# THS7002CPWP_Schematic.net
KiCad netlist of a schematic drawn in Altium Designer
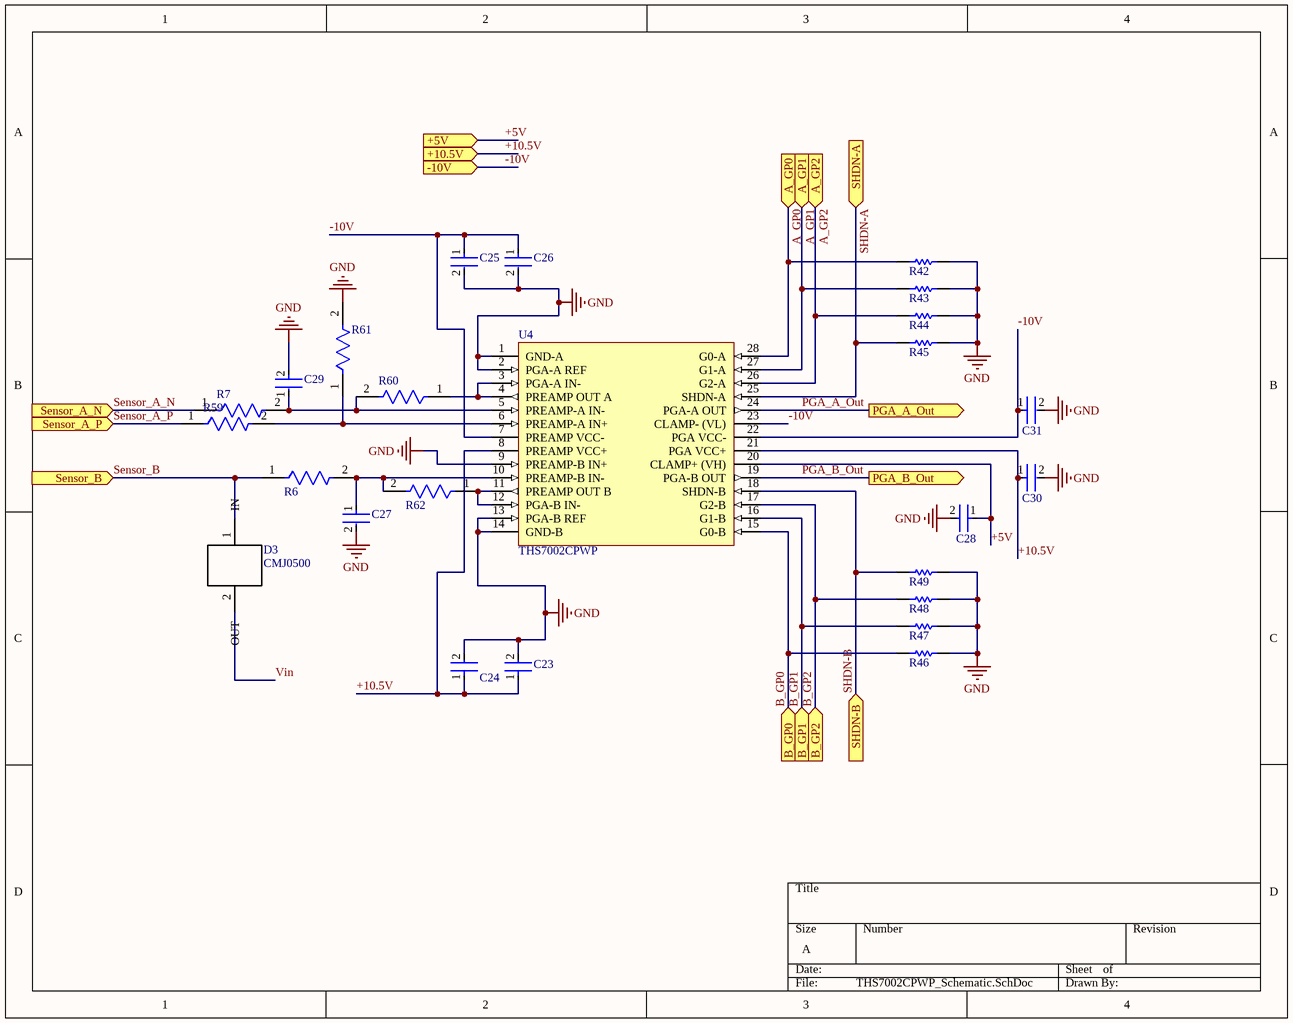
[diagram p0: THS7002CPWP_Schematic.SchDoc]

(export (version "E")
  (design (tool "Eeschema 10.0.6"))
  (components
    (comp (ref "C23")
      (value "~")
      (footprint "FP-C2012-060-0_2-IPC_A")
      (description "Multilayer Ceramic Capacitors 6.8μF ±10% 10V JB SMD 0805")
      (fields (field (name "TOLERANCE") "10%"))
      (libsource (lib "Capacitors") (part "CMP-08246-004641-1"))
    )
    (comp (ref "C24")
      (value "CC0603KRX7R7BB104")
      (footprint "FP-CC0603-DA-MFG")
      (description "CAP CER 0.1UF 16V X7R 0603")
      (fields
        (field (name "OCTOPART") "https://octopart.com/cc0603krx7r7bb104-yageo-192941")
        (field (name "TOLERANCE") "0.1")
      )
      (libsource (lib "Altium Content Vault") (part "11868f565c42a9108669ba33697ecf6"))
    )
    (comp (ref "C25")
      (value "CC0603KRX7R7BB104")
      (footprint "FP-CC0603-DA-MFG")
      (description "CAP CER 0.1UF 16V X7R 0603")
      (fields
        (field (name "OCTOPART") "https://octopart.com/cc0603krx7r7bb104-yageo-192941")
        (field (name "TOLERANCE") "0.1")
      )
      (libsource (lib "Altium Content Vault") (part "11868f565c42a9108669ba33697ecf6"))
    )
    (comp (ref "C26")
      (value "~")
      (footprint "FP-C2012-060-0_2-IPC_A")
      (description "Multilayer Ceramic Capacitors 6.8μF ±10% 10V JB SMD 0805")
      (fields (field (name "TOLERANCE") "10%"))
      (libsource (lib "Capacitors") (part "b4654b650e69147ec39a6b967a45e02"))
    )
    (comp (ref "C27")
      (value "GRM2195C1H622JA01D")
      (footprint "FP-GRM219-0_1-IPC_C")
      (description "Chip Multilayer Ceramic Capacitors for General Purpose, 0805, 6200pF, C0G, 30ppm/°C, 5%, 50V")
      (fields (field (name "TOLERANCE") "5%") (field (name "VOLTAGE") "50V"))
      (libsource (lib "Altium Content Vault") (part "02cd4be3c70576c341d710602a673aa"))
    )
    (comp (ref "C28")
      (value "~")
      (footprint "FP-C2012-060-0_2-IPC_A")
      (description "Multilayer Ceramic Capacitors 6.8μF ±10% 10V JB SMD 0805")
      (fields (field (name "TOLERANCE") "10%"))
      (libsource (lib "Capacitors") (part "b4654b650e69147ec39a6b967a45e02"))
    )
    (comp (ref "C29")
      (value "GRM2165C1H302JA01D")
      (footprint "FP-GRM216-0_1-IPC_A")
      (description "Chip Multilayer Ceramic Capacitors for General Purpose, 0805, 3000pF, C0G, 30ppm/°C, 5%, 50V")
      (fields (field (name "VOLTAGE") "50V") (field (name "TOLERANCE") "5%"))
      (libsource (lib "Altium Content Vault") (part "236180d848d6139a670b325ea6854c9"))
    )
    (comp (ref "C30")
      (value "CC0603KRX7R7BB104")
      (footprint "FP-CC0603-DA-MFG")
      (description "CAP CER 0.1UF 16V X7R 0603")
      (fields
        (field (name "OCTOPART") "https://octopart.com/cc0603krx7r7bb104-yageo-192941")
        (field (name "TOLERANCE") "0.1")
      )
      (libsource (lib "Altium Content Vault") (part "11868f565c42a9108669ba33697ecf6"))
    )
    (comp (ref "C31")
      (value "CC0603KRX7R7BB104")
      (footprint "FP-CC0603-DA-MFG")
      (description "CAP CER 0.1UF 16V X7R 0603")
      (fields
        (field (name "OCTOPART") "https://octopart.com/cc0603krx7r7bb104-yageo-192941")
        (field (name "TOLERANCE") "0.1")
      )
      (libsource (lib "Altium Content Vault") (part "11868f565c42a9108669ba33697ecf6"))
    )
    (comp (ref "D3")
      (value "CMJ0500")
      (footprint "CMJ2000_Footprint")
      (description "CMJ0500: DIODE CUR REG 100V 0.5mA 500MW")
      (libsource (lib "CMJ2000_Schematic") (part "CMJ2000/0130"))
    )
    (comp (ref "R6")
      (value "CRCW0603499RFKEA")
      (footprint "FP-CRCW0603-e3-MFG")
      (description "RES Thick Film, 499Ω, 1%, 0.1W, 100ppm/°C, 0603")
      (fields (field (name "TOLERANCE") "1%"))
      (libsource (lib "Altium Content Vault") (part "1029c3af85768c4190bb7ad29bc67b5"))
    )
    (comp (ref "R7")
      (value "CRCW0603499RFKEA")
      (footprint "FP-CRCW0603-e3-MFG")
      (description "RES Thick Film, 499Ω, 1%, 0.1W, 100ppm/°C, 0603")
      (fields (field (name "TOLERANCE") "1%"))
      (libsource (lib "Altium Content Vault") (part "1029c3af85768c4190bb7ad29bc67b5"))
    )
    (comp (ref "R42")
      (value "RC0603FR-073K3L")
      (footprint "RESC1608X55X25ML10T15")
      (description "Chip Resistor, 3.3 KOhm, +/- 1%, 0.1 W, -55 to 155 degC, 0603 (1608 Metric), RoHS, Tape and Reel")
      (fields (field (name "MANUFACTURER") "Yageo") (field (name "TOLERANCE") "1%"))
      (libsource (lib "Altium Content Vault") (part "RES-2"))
    )
    (comp (ref "R43")
      (value "RC0603FR-073K3L")
      (footprint "RESC1608X55X25ML10T15")
      (description "Chip Resistor, 3.3 KOhm, +/- 1%, 0.1 W, -55 to 155 degC, 0603 (1608 Metric), RoHS, Tape and Reel")
      (fields (field (name "MANUFACTURER") "Yageo") (field (name "TOLERANCE") "1%"))
      (libsource (lib "Altium Content Vault") (part "RES-2"))
    )
    (comp (ref "R44")
      (value "RC0603FR-073K3L")
      (footprint "RESC1608X55X25ML10T15")
      (description "Chip Resistor, 3.3 KOhm, +/- 1%, 0.1 W, -55 to 155 degC, 0603 (1608 Metric), RoHS, Tape and Reel")
      (fields (field (name "MANUFACTURER") "Yageo") (field (name "TOLERANCE") "1%"))
      (libsource (lib "Altium Content Vault") (part "RES-2"))
    )
    (comp (ref "R45")
      (value "RC0603FR-073K3L")
      (footprint "RESC1608X55X25ML10T15")
      (description "Chip Resistor, 3.3 KOhm, +/- 1%, 0.1 W, -55 to 155 degC, 0603 (1608 Metric), RoHS, Tape and Reel")
      (fields (field (name "MANUFACTURER") "Yageo") (field (name "TOLERANCE") "1%"))
      (libsource (lib "Altium Content Vault") (part "RES-2"))
    )
    (comp (ref "R46")
      (value "RC0603FR-073K3L")
      (footprint "RESC1608X55X25ML10T15")
      (description "Chip Resistor, 3.3 KOhm, +/- 1%, 0.1 W, -55 to 155 degC, 0603 (1608 Metric), RoHS, Tape and Reel")
      (fields (field (name "MANUFACTURER") "Yageo") (field (name "TOLERANCE") "1%"))
      (libsource (lib "Altium Content Vault") (part "RES-2"))
    )
    (comp (ref "R47")
      (value "RC0603FR-073K3L")
      (footprint "RESC1608X55X25ML10T15")
      (description "Chip Resistor, 3.3 KOhm, +/- 1%, 0.1 W, -55 to 155 degC, 0603 (1608 Metric), RoHS, Tape and Reel")
      (fields (field (name "MANUFACTURER") "Yageo") (field (name "TOLERANCE") "1%"))
      (libsource (lib "Altium Content Vault") (part "RES-2"))
    )
    (comp (ref "R48")
      (value "RC0603FR-073K3L")
      (footprint "RESC1608X55X25ML10T15")
      (description "Chip Resistor, 3.3 KOhm, +/- 1%, 0.1 W, -55 to 155 degC, 0603 (1608 Metric), RoHS, Tape and Reel")
      (fields (field (name "MANUFACTURER") "Yageo") (field (name "TOLERANCE") "1%"))
      (libsource (lib "Altium Content Vault") (part "RES-2"))
    )
    (comp (ref "R49")
      (value "RC0603FR-073K3L")
      (footprint "RESC1608X55X25ML10T15")
      (description "Chip Resistor, 3.3 KOhm, +/- 1%, 0.1 W, -55 to 155 degC, 0603 (1608 Metric), RoHS, Tape and Reel")
      (fields (field (name "MANUFACTURER") "Yageo") (field (name "TOLERANCE") "1%"))
      (libsource (lib "Altium Content Vault") (part "RES-2"))
    )
    (comp (ref "R59")
      (value "CRCW0603499RFKEA")
      (footprint "FP-CRCW0603-e3-MFG")
      (description "RES Thick Film, 499Ω, 1%, 0.1W, 100ppm/°C, 0603")
      (fields (field (name "TOLERANCE") "1%"))
      (libsource (lib "Altium Content Vault") (part "1029c3af85768c4190bb7ad29bc67b5"))
    )
    (comp (ref "R60")
      (value "CRCW0603499RFKEA")
      (footprint "FP-CRCW0603-e3-MFG")
      (description "RES Thick Film, 499Ω, 1%, 0.1W, 100ppm/°C, 0603")
      (fields (field (name "TOLERANCE") "1%"))
      (libsource (lib "Altium Content Vault") (part "1029c3af85768c4190bb7ad29bc67b5"))
    )
    (comp (ref "R61")
      (value "CRCW0603499RFKEA")
      (footprint "FP-CRCW0603-e3-MFG")
      (description "RES Thick Film, 499Ω, 1%, 0.1W, 100ppm/°C, 0603")
      (fields (field (name "TOLERANCE") "1%"))
      (libsource (lib "Altium Content Vault") (part "1029c3af85768c4190bb7ad29bc67b5"))
    )
    (comp (ref "R62")
      (value "CRCW0603499RFKEA")
      (footprint "FP-CRCW0603-e3-MFG")
      (description "RES Thick Film, 499Ω, 1%, 0.1W, 100ppm/°C, 0603")
      (fields (field (name "TOLERANCE") "1%"))
      (libsource (lib "Altium Content Vault") (part "1029c3af85768c4190bb7ad29bc67b5"))
    )
    (comp (ref "U4")
      (value "THS7002CPWP")
      (footprint "THS7002CPWP")
      (fields (field (name "MANUFACTURER") "Texas Instruments"))
      (libsource (lib "THS7002CPWP_Symbol") (part "CMP-0988-00132-2"))
    )
  )
  (nets
    (net (code "1") (name "/+5V") (class "Default")
      (node (ref "C28") (pin "1") (pinfunction "1_1") (pintype "passive"))
      (node (ref "U4") (pin "20") (pinfunction "CLAMP+_(VH)_20") (pintype "power_in"))
    )
    (net (code "2") (name "/+10.5V") (class "Default")
      (node (ref "C23") (pin "1") (pinfunction "1_1") (pintype "passive"))
      (node (ref "C24") (pin "1") (pinfunction "1_1") (pintype "passive"))
      (node (ref "C30") (pin "1") (pinfunction "1_1") (pintype "passive"))
      (node (ref "U4") (pin "21") (pinfunction "PGA_VCC+_21") (pintype "power_in"))
      (node (ref "U4") (pin "8") (pinfunction "PREAMP_VCC+_8") (pintype "power_in"))
    )
    (net (code "3") (name "/-10V") (class "Default")
      (node (ref "C25") (pin "1") (pinfunction "1_1") (pintype "passive"))
      (node (ref "C26") (pin "1") (pinfunction "1_1") (pintype "passive"))
      (node (ref "C31") (pin "1") (pinfunction "1_1") (pintype "passive"))
      (node (ref "U4") (pin "22") (pinfunction "PGA_VCC-_22") (pintype "power_in"))
      (node (ref "U4") (pin "23") (pinfunction "CLAMP-_(VL)_23") (pintype "power_in"))
      (node (ref "U4") (pin "7") (pinfunction "PREAMP_VCC-_7") (pintype "power_in"))
    )
    (net (code "4") (name "/A_GP0") (class "Default")
      (node (ref "R42") (pin "2") (pinfunction "2_2") (pintype "passive"))
      (node (ref "U4") (pin "28") (pinfunction "G0-A_28") (pintype "input"))
    )
    (net (code "5") (name "/A_GP1") (class "Default")
      (node (ref "R43") (pin "2") (pinfunction "2_2") (pintype "passive"))
      (node (ref "U4") (pin "27") (pinfunction "G1-A_27") (pintype "input"))
    )
    (net (code "6") (name "/A_GP2") (class "Default")
      (node (ref "R44") (pin "2") (pinfunction "2_2") (pintype "passive"))
      (node (ref "U4") (pin "26") (pinfunction "G2-A_26") (pintype "input"))
    )
    (net (code "7") (name "/B_GP0") (class "Default")
      (node (ref "R46") (pin "2") (pinfunction "2_2") (pintype "passive"))
      (node (ref "U4") (pin "15") (pinfunction "G0-B_15") (pintype "input"))
    )
    (net (code "8") (name "/B_GP1") (class "Default")
      (node (ref "R47") (pin "2") (pinfunction "2_2") (pintype "passive"))
      (node (ref "U4") (pin "16") (pinfunction "G1-B_16") (pintype "input"))
    )
    (net (code "9") (name "/B_GP2") (class "Default")
      (node (ref "R48") (pin "2") (pinfunction "2_2") (pintype "passive"))
      (node (ref "U4") (pin "17") (pinfunction "G2-B_17") (pintype "input"))
    )
    (net (code "10") (name "/PGA_A_Out") (class "Default")
      (node (ref "U4") (pin "24") (pinfunction "PGA-A_OUT_24") (pintype "output"))
    )
    (net (code "11") (name "/PGA_B_Out") (class "Default")
      (node (ref "U4") (pin "19") (pinfunction "PGA-B_OUT_19") (pintype "output"))
    )
    (net (code "12") (name "/SHDN-A") (class "Default")
      (node (ref "R45") (pin "2") (pinfunction "2_2") (pintype "passive"))
      (node (ref "U4") (pin "25") (pinfunction "SHDN-A_25") (pintype "input"))
    )
    (net (code "13") (name "/SHDN-B") (class "Default")
      (node (ref "R49") (pin "2") (pinfunction "2_2") (pintype "passive"))
      (node (ref "U4") (pin "18") (pinfunction "SHDN-B_18") (pintype "input"))
    )
    (net (code "14") (name "/Sensor_A_N") (class "Default")
      (node (ref "R7") (pin "1") (pinfunction "1_1") (pintype "passive"))
    )
    (net (code "15") (name "/Sensor_A_P") (class "Default")
      (node (ref "R59") (pin "1") (pinfunction "1_1") (pintype "passive"))
    )
    (net (code "16") (name "/Sensor_B") (class "Default")
      (node (ref "R6") (pin "1") (pinfunction "1_1") (pintype "passive"))
    )
    (net (code "18") (name "GND") (class "Default")
      (node (ref "C23") (pin "2") (pinfunction "2_2") (pintype "passive"))
      (node (ref "C24") (pin "2") (pinfunction "2_2") (pintype "passive"))
      (node (ref "C25") (pin "2") (pinfunction "2_2") (pintype "passive"))
      (node (ref "C26") (pin "2") (pinfunction "2_2") (pintype "passive"))
      (node (ref "C27") (pin "2") (pinfunction "2_2") (pintype "passive"))
      (node (ref "C28") (pin "2") (pinfunction "2_2") (pintype "passive"))
      (node (ref "C29") (pin "2") (pinfunction "2_2") (pintype "passive"))
      (node (ref "C30") (pin "2") (pinfunction "2_2") (pintype "passive"))
      (node (ref "C31") (pin "2") (pinfunction "2_2") (pintype "passive"))
      (node (ref "R42") (pin "1") (pinfunction "1_1") (pintype "passive"))
      (node (ref "R43") (pin "1") (pinfunction "1_1") (pintype "passive"))
      (node (ref "R44") (pin "1") (pinfunction "1_1") (pintype "passive"))
      (node (ref "R45") (pin "1") (pinfunction "1_1") (pintype "passive"))
      (node (ref "R46") (pin "1") (pinfunction "1_1") (pintype "passive"))
      (node (ref "R47") (pin "1") (pinfunction "1_1") (pintype "passive"))
      (node (ref "R48") (pin "1") (pinfunction "1_1") (pintype "passive"))
      (node (ref "R49") (pin "1") (pinfunction "1_1") (pintype "passive"))
      (node (ref "R61") (pin "2") (pinfunction "2_2") (pintype "passive"))
      (node (ref "U4") (pin "1") (pinfunction "GND-A_1") (pintype "power_in"))
      (node (ref "U4") (pin "13") (pinfunction "PGA-B_REF_13") (pintype "input"))
      (node (ref "U4") (pin "14") (pinfunction "GND-B_14") (pintype "power_in"))
      (node (ref "U4") (pin "2") (pinfunction "PGA-A_REF_2") (pintype "input"))
      (node (ref "U4") (pin "9") (pinfunction "PREAMP-B_IN+_9") (pintype "input"))
    )
    (net (code "19") (name "Net-(U4-PGA-A_IN-)") (class "Default")
      (node (ref "R60") (pin "1") (pinfunction "1_1") (pintype "passive"))
      (node (ref "U4") (pin "3") (pinfunction "PGA-A_IN-_3") (pintype "input"))
      (node (ref "U4") (pin "4") (pinfunction "PREAMP_OUT_A_4") (pintype "output"))
    )
    (net (code "20") (name "Net-(U4-PGA-B_IN-)") (class "Default")
      (node (ref "R62") (pin "1") (pinfunction "1_1") (pintype "passive"))
      (node (ref "U4") (pin "11") (pinfunction "PREAMP_OUT_B_11") (pintype "output"))
      (node (ref "U4") (pin "12") (pinfunction "PGA-B_IN-_12") (pintype "input"))
    )
    (net (code "21") (name "Net-(U4-PREAMP-A_IN+)") (class "Default")
      (node (ref "R59") (pin "2") (pinfunction "2_2") (pintype "passive"))
      (node (ref "R61") (pin "1") (pinfunction "1_1") (pintype "passive"))
      (node (ref "U4") (pin "6") (pinfunction "PREAMP-A_IN+_6") (pintype "input"))
    )
    (net (code "22") (name "Net-(U4-PREAMP-A_IN-)") (class "Default")
      (node (ref "C29") (pin "1") (pinfunction "1_1") (pintype "passive"))
      (node (ref "R60") (pin "2") (pinfunction "2_2") (pintype "passive"))
      (node (ref "R7") (pin "2") (pinfunction "2_2") (pintype "passive"))
      (node (ref "U4") (pin "5") (pinfunction "PREAMP-A_IN-_5") (pintype "input"))
    )
    (net (code "23") (name "Net-(U4-PREAMP-B_IN-)") (class "Default")
      (node (ref "C27") (pin "1") (pinfunction "1_1") (pintype "passive"))
      (node (ref "R6") (pin "2") (pinfunction "2_2") (pintype "passive"))
      (node (ref "R62") (pin "2") (pinfunction "2_2") (pintype "passive"))
      (node (ref "U4") (pin "10") (pinfunction "PREAMP-B_IN-_10") (pintype "input"))
    )
    (net (code "24") (name "unconnected-(D3-IN-Pad1)") (class "Default")
      (node (ref "D3") (pin "1") (pinfunction "IN_1") (pintype "passive"))
    )
    (net (code "25") (name "unconnected-(D3-OUT-Pad2)") (class "Default")
      (node (ref "D3") (pin "2") (pinfunction "OUT_2") (pintype "passive"))
    )
  )
)
